# MCPEmulate1.net
KiCad netlist of a schematic drawn in Altium Designer
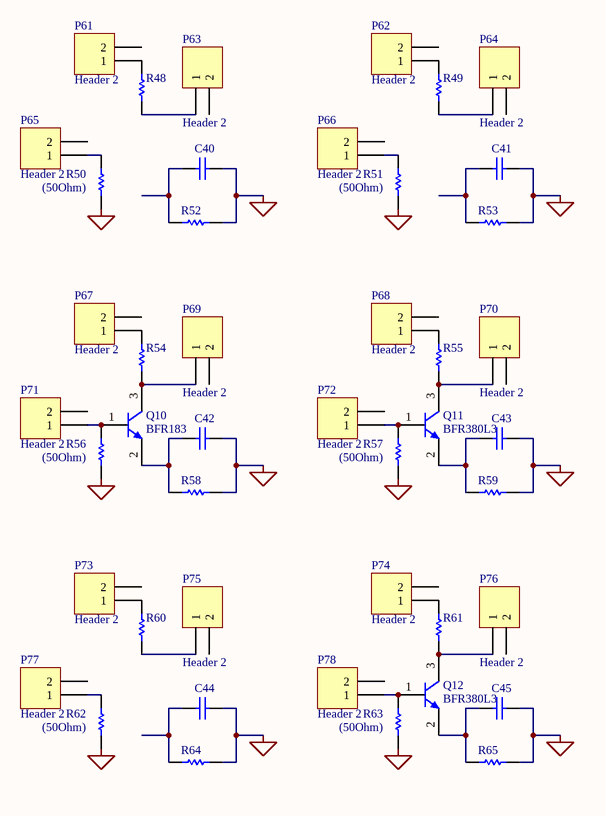
[diagram p0: MCPEmulate1.SchDoc]

(export (version "E")
  (design (tool "Eeschema 10.0.6"))
  (components
    (comp (ref "C40")
      (value "~")
      (footprint "CAPC2013X140X45NL15T25")
      (description "0402")
      (fields (field (name "PART NUMBER") "GRM21BR71A106KE51L") (field (name "MANUFACTURER") "Murata"))
      (libsource (lib "Altium Content Vault") (part "CAP"))
    )
    (comp (ref "C41")
      (value "~")
      (footprint "CAPC2013X140X45NL15T25")
      (description "0402")
      (fields (field (name "PART NUMBER") "GRM21BR71A106KE51L") (field (name "MANUFACTURER") "Murata"))
      (libsource (lib "Altium Content Vault") (part "CAP"))
    )
    (comp (ref "C42")
      (value "~")
      (footprint "CAPC2013X140X45NL15T25")
      (description "0402")
      (fields (field (name "PART NUMBER") "GRM21BR71A106KE51L") (field (name "MANUFACTURER") "Murata"))
      (libsource (lib "Altium Content Vault") (part "CAP"))
    )
    (comp (ref "C43")
      (value "~")
      (footprint "CAPC2013X140X45NL15T25")
      (description "0402")
      (fields (field (name "PART NUMBER") "GRM21BR71A106KE51L") (field (name "MANUFACTURER") "Murata"))
      (libsource (lib "Altium Content Vault") (part "CAP"))
    )
    (comp (ref "C44")
      (value "~")
      (footprint "CAPC2013X140X45NL15T25")
      (description "0402")
      (fields (field (name "PART NUMBER") "GRM21BR71A106KE51L") (field (name "MANUFACTURER") "Murata"))
      (libsource (lib "Altium Content Vault") (part "CAP"))
    )
    (comp (ref "C45")
      (value "~")
      (footprint "CAPC2013X140X45NL15T25")
      (description "0402")
      (fields (field (name "PART NUMBER") "GRM21BR71A106KE51L") (field (name "MANUFACTURER") "Murata"))
      (libsource (lib "Altium Content Vault") (part "CAP"))
    )
    (comp (ref "P61")
      (value "Header 2")
      (footprint "HDR1X2")
      (description "Header, 2-Pin")
      (fields (field (name "PUBLISHER") "Altium Limited"))
      (libsource (lib "Miscellaneous Connectors") (part "Header 2"))
    )
    (comp (ref "P62")
      (value "Header 2")
      (footprint "HDR1X2")
      (description "Header, 2-Pin")
      (fields (field (name "PUBLISHER") "Altium Limited"))
      (libsource (lib "Miscellaneous Connectors") (part "Header 2"))
    )
    (comp (ref "P63")
      (value "Header 2")
      (footprint "HDR1X2")
      (description "Header, 2-Pin")
      (fields (field (name "PUBLISHER") "Altium Limited"))
      (libsource (lib "") (part "Header 2_1"))
    )
    (comp (ref "P64")
      (value "Header 2")
      (footprint "HDR1X2")
      (description "Header, 2-Pin")
      (fields (field (name "PUBLISHER") "Altium Limited"))
      (libsource (lib "") (part "Header 2_1"))
    )
    (comp (ref "P65")
      (value "Header 2")
      (footprint "HDR1X2")
      (description "Header, 2-Pin")
      (fields (field (name "PUBLISHER") "Altium Limited"))
      (libsource (lib "Miscellaneous Connectors") (part "Header 2"))
    )
    (comp (ref "P66")
      (value "Header 2")
      (footprint "HDR1X2")
      (description "Header, 2-Pin")
      (fields (field (name "PUBLISHER") "Altium Limited"))
      (libsource (lib "Miscellaneous Connectors") (part "Header 2"))
    )
    (comp (ref "P67")
      (value "Header 2")
      (footprint "HDR1X2")
      (description "Header, 2-Pin")
      (fields (field (name "PUBLISHER") "Altium Limited"))
      (libsource (lib "Miscellaneous Connectors") (part "Header 2"))
    )
    (comp (ref "P68")
      (value "Header 2")
      (footprint "HDR1X2")
      (description "Header, 2-Pin")
      (fields (field (name "PUBLISHER") "Altium Limited"))
      (libsource (lib "Miscellaneous Connectors") (part "Header 2"))
    )
    (comp (ref "P69")
      (value "Header 2")
      (footprint "HDR1X2")
      (description "Header, 2-Pin")
      (fields (field (name "PUBLISHER") "Altium Limited"))
      (libsource (lib "") (part "Header 2_1"))
    )
    (comp (ref "P70")
      (value "Header 2")
      (footprint "HDR1X2")
      (description "Header, 2-Pin")
      (fields (field (name "PUBLISHER") "Altium Limited"))
      (libsource (lib "") (part "Header 2_1"))
    )
    (comp (ref "P71")
      (value "Header 2")
      (footprint "HDR1X2")
      (description "Header, 2-Pin")
      (fields (field (name "PUBLISHER") "Altium Limited"))
      (libsource (lib "Miscellaneous Connectors") (part "Header 2"))
    )
    (comp (ref "P72")
      (value "Header 2")
      (footprint "HDR1X2")
      (description "Header, 2-Pin")
      (fields (field (name "PUBLISHER") "Altium Limited"))
      (libsource (lib "Miscellaneous Connectors") (part "Header 2"))
    )
    (comp (ref "P73")
      (value "Header 2")
      (footprint "HDR1X2")
      (description "Header, 2-Pin")
      (fields (field (name "PUBLISHER") "Altium Limited"))
      (libsource (lib "Miscellaneous Connectors") (part "Header 2"))
    )
    (comp (ref "P74")
      (value "Header 2")
      (footprint "HDR1X2")
      (description "Header, 2-Pin")
      (fields (field (name "PUBLISHER") "Altium Limited"))
      (libsource (lib "Miscellaneous Connectors") (part "Header 2"))
    )
    (comp (ref "P75")
      (value "Header 2")
      (footprint "HDR1X2")
      (description "Header, 2-Pin")
      (fields (field (name "PUBLISHER") "Altium Limited"))
      (libsource (lib "") (part "Header 2_1"))
    )
    (comp (ref "P76")
      (value "Header 2")
      (footprint "HDR1X2")
      (description "Header, 2-Pin")
      (fields (field (name "PUBLISHER") "Altium Limited"))
      (libsource (lib "") (part "Header 2_1"))
    )
    (comp (ref "P77")
      (value "Header 2")
      (footprint "HDR1X2")
      (description "Header, 2-Pin")
      (fields (field (name "PUBLISHER") "Altium Limited"))
      (libsource (lib "Miscellaneous Connectors") (part "Header 2"))
    )
    (comp (ref "P78")
      (value "Header 2")
      (footprint "HDR1X2")
      (description "Header, 2-Pin")
      (fields (field (name "PUBLISHER") "Altium Limited"))
      (libsource (lib "Miscellaneous Connectors") (part "Header 2"))
    )
    (comp (ref "Q10")
      (value "BFR183")
      (footprint "INF-SOT23_M")
      (description "NPN Silicon RF Transistor, 12 V VCEO, 65 mA IC, 17.5 dB Gmax, SOT23, Green")
      (fields (field (name "MANUFACTURER") "Infineon"))
      (libsource (lib "Altium Content Vault") (part "INF-BFR183-3"))
    )
    (comp (ref "Q11")
      (value "BFR380L3")
      (footprint "INF-TSLP-3-1_V")
      (description "NPN Silicon RF Transistor, 6 V VCEO, 80 mA IC, 13.5 dB Gmax, TSLP-3-1, Green")
      (fields (field (name "MANUFACTURER") "Infineon"))
      (libsource (lib "Altium Content Vault") (part "INF-BFR380L3-3"))
    )
    (comp (ref "Q12")
      (value "BFR380L3")
      (footprint "INF-TSLP-3-1_V")
      (description "NPN Silicon RF Transistor, 6 V VCEO, 80 mA IC, 13.5 dB Gmax, TSLP-3-1, Green")
      (fields (field (name "MANUFACTURER") "Infineon"))
      (libsource (lib "Altium Content Vault") (part "INF-BFR380L3-3"))
    )
    (comp (ref "R48")
      (value "~")
      (footprint "RESC1005X40X25NL05T10")
      (description "0402")
      (fields (field (name "PART NUMBER") "RC0402FR-071KL") (field (name "MANUFACTURER") "Yageo / Phycomp"))
      (libsource (lib "Altium Content Vault") (part "RES"))
    )
    (comp (ref "R49")
      (value "~")
      (footprint "RESC1005X40X25NL05T10")
      (description "0402")
      (fields (field (name "PART NUMBER") "RC0402FR-071KL") (field (name "MANUFACTURER") "Yageo / Phycomp"))
      (libsource (lib "Altium Content Vault") (part "RES"))
    )
    (comp (ref "R50")
      (value "(50Ohm)")
      (footprint "RESC1005X40X25NL05T10")
      (description "0402")
      (fields (field (name "PART NUMBER") "RC0402FR-071KL") (field (name "MANUFACTURER") "Yageo / Phycomp"))
      (libsource (lib "Altium Content Vault") (part "RES"))
    )
    (comp (ref "R51")
      (value "(50Ohm)")
      (footprint "RESC1005X40X25NL05T10")
      (description "0402")
      (fields (field (name "PART NUMBER") "RC0402FR-071KL") (field (name "MANUFACTURER") "Yageo / Phycomp"))
      (libsource (lib "Altium Content Vault") (part "RES"))
    )
    (comp (ref "R52")
      (value "~")
      (footprint "RESC1005X40X25NL05T10")
      (description "0402")
      (fields (field (name "PART NUMBER") "RC0402FR-071KL") (field (name "MANUFACTURER") "Yageo / Phycomp"))
      (libsource (lib "Altium Content Vault") (part "RES"))
    )
    (comp (ref "R53")
      (value "~")
      (footprint "RESC1005X40X25NL05T10")
      (description "0402")
      (fields (field (name "PART NUMBER") "RC0402FR-071KL") (field (name "MANUFACTURER") "Yageo / Phycomp"))
      (libsource (lib "Altium Content Vault") (part "RES"))
    )
    (comp (ref "R54")
      (value "~")
      (footprint "RESC1005X40X25NL05T10")
      (description "0402")
      (fields (field (name "PART NUMBER") "RC0402FR-071KL") (field (name "MANUFACTURER") "Yageo / Phycomp"))
      (libsource (lib "Altium Content Vault") (part "RES"))
    )
    (comp (ref "R55")
      (value "~")
      (footprint "RESC1005X40X25NL05T10")
      (description "0402")
      (fields (field (name "PART NUMBER") "RC0402FR-071KL") (field (name "MANUFACTURER") "Yageo / Phycomp"))
      (libsource (lib "Altium Content Vault") (part "RES"))
    )
    (comp (ref "R56")
      (value "(50Ohm)")
      (footprint "RESC1005X40X25NL05T10")
      (description "0402")
      (fields (field (name "PART NUMBER") "RC0402FR-071KL") (field (name "MANUFACTURER") "Yageo / Phycomp"))
      (libsource (lib "Altium Content Vault") (part "RES"))
    )
    (comp (ref "R57")
      (value "(50Ohm)")
      (footprint "RESC1005X40X25NL05T10")
      (description "0402")
      (fields (field (name "PART NUMBER") "RC0402FR-071KL") (field (name "MANUFACTURER") "Yageo / Phycomp"))
      (libsource (lib "Altium Content Vault") (part "RES"))
    )
    (comp (ref "R58")
      (value "~")
      (footprint "RESC1005X40X25NL05T10")
      (description "0402")
      (fields (field (name "PART NUMBER") "RC0402FR-071KL") (field (name "MANUFACTURER") "Yageo / Phycomp"))
      (libsource (lib "Altium Content Vault") (part "RES"))
    )
    (comp (ref "R59")
      (value "~")
      (footprint "RESC1005X40X25NL05T10")
      (description "0402")
      (fields (field (name "PART NUMBER") "RC0402FR-071KL") (field (name "MANUFACTURER") "Yageo / Phycomp"))
      (libsource (lib "Altium Content Vault") (part "RES"))
    )
    (comp (ref "R60")
      (value "~")
      (footprint "RESC1005X40X25NL05T10")
      (description "0402")
      (fields (field (name "PART NUMBER") "RC0402FR-071KL") (field (name "MANUFACTURER") "Yageo / Phycomp"))
      (libsource (lib "Altium Content Vault") (part "RES"))
    )
    (comp (ref "R61")
      (value "~")
      (footprint "RESC1005X40X25NL05T10")
      (description "0402")
      (fields (field (name "PART NUMBER") "RC0402FR-071KL") (field (name "MANUFACTURER") "Yageo / Phycomp"))
      (libsource (lib "Altium Content Vault") (part "RES"))
    )
    (comp (ref "R62")
      (value "(50Ohm)")
      (footprint "RESC1005X40X25NL05T10")
      (description "0402")
      (fields (field (name "PART NUMBER") "RC0402FR-071KL") (field (name "MANUFACTURER") "Yageo / Phycomp"))
      (libsource (lib "Altium Content Vault") (part "RES"))
    )
    (comp (ref "R63")
      (value "(50Ohm)")
      (footprint "RESC1005X40X25NL05T10")
      (description "0402")
      (fields (field (name "PART NUMBER") "RC0402FR-071KL") (field (name "MANUFACTURER") "Yageo / Phycomp"))
      (libsource (lib "Altium Content Vault") (part "RES"))
    )
    (comp (ref "R64")
      (value "~")
      (footprint "RESC1005X40X25NL05T10")
      (description "0402")
      (fields (field (name "PART NUMBER") "RC0402FR-071KL") (field (name "MANUFACTURER") "Yageo / Phycomp"))
      (libsource (lib "Altium Content Vault") (part "RES"))
    )
    (comp (ref "R65")
      (value "~")
      (footprint "RESC1005X40X25NL05T10")
      (description "0402")
      (fields (field (name "PART NUMBER") "RC0402FR-071KL") (field (name "MANUFACTURER") "Yageo / Phycomp"))
      (libsource (lib "Altium Content Vault") (part "RES"))
    )
  )
  (nets
    (net (code "1") (name "GND") (class "Default")
      (node (ref "C40") (pin "1") (pinfunction "1_1") (pintype "passive"))
      (node (ref "C41") (pin "1") (pinfunction "1_1") (pintype "passive"))
      (node (ref "C42") (pin "1") (pinfunction "1_1") (pintype "passive"))
      (node (ref "C43") (pin "1") (pinfunction "1_1") (pintype "passive"))
      (node (ref "C44") (pin "1") (pinfunction "1_1") (pintype "passive"))
      (node (ref "C45") (pin "1") (pinfunction "1_1") (pintype "passive"))
      (node (ref "R50") (pin "1") (pinfunction "1_1") (pintype "passive"))
      (node (ref "R51") (pin "1") (pinfunction "1_1") (pintype "passive"))
      (node (ref "R52") (pin "1") (pinfunction "1_1") (pintype "passive"))
      (node (ref "R53") (pin "1") (pinfunction "1_1") (pintype "passive"))
      (node (ref "R56") (pin "1") (pinfunction "1_1") (pintype "passive"))
      (node (ref "R57") (pin "1") (pinfunction "1_1") (pintype "passive"))
      (node (ref "R58") (pin "1") (pinfunction "1_1") (pintype "passive"))
      (node (ref "R59") (pin "1") (pinfunction "1_1") (pintype "passive"))
      (node (ref "R62") (pin "1") (pinfunction "1_1") (pintype "passive"))
      (node (ref "R63") (pin "1") (pinfunction "1_1") (pintype "passive"))
      (node (ref "R64") (pin "1") (pinfunction "1_1") (pintype "passive"))
      (node (ref "R65") (pin "1") (pinfunction "1_1") (pintype "passive"))
    )
    (net (code "2") (name "Net-(C40-Pad2)") (class "Default")
      (node (ref "C40") (pin "2") (pinfunction "2_2") (pintype "passive"))
      (node (ref "R52") (pin "2") (pinfunction "2_2") (pintype "passive"))
    )
    (net (code "3") (name "Net-(C41-Pad2)") (class "Default")
      (node (ref "C41") (pin "2") (pinfunction "2_2") (pintype "passive"))
      (node (ref "R53") (pin "2") (pinfunction "2_2") (pintype "passive"))
    )
    (net (code "4") (name "Net-(C44-Pad2)") (class "Default")
      (node (ref "C44") (pin "2") (pinfunction "2_2") (pintype "passive"))
      (node (ref "R64") (pin "2") (pinfunction "2_2") (pintype "passive"))
    )
    (net (code "5") (name "Net-(P61-Pad1)") (class "Default")
      (node (ref "P61") (pin "1") (pinfunction "1_1") (pintype "passive"))
      (node (ref "R48") (pin "1") (pinfunction "1_1") (pintype "passive"))
    )
    (net (code "6") (name "Net-(P62-Pad1)") (class "Default")
      (node (ref "P62") (pin "1") (pinfunction "1_1") (pintype "passive"))
      (node (ref "R49") (pin "1") (pinfunction "1_1") (pintype "passive"))
    )
    (net (code "7") (name "Net-(P63-Pad1)") (class "Default")
      (node (ref "P63") (pin "1") (pinfunction "1_1") (pintype "passive"))
      (node (ref "R48") (pin "2") (pinfunction "2_2") (pintype "passive"))
    )
    (net (code "8") (name "Net-(P64-Pad1)") (class "Default")
      (node (ref "P64") (pin "1") (pinfunction "1_1") (pintype "passive"))
      (node (ref "R49") (pin "2") (pinfunction "2_2") (pintype "passive"))
    )
    (net (code "9") (name "Net-(P65-Pad1)") (class "Default")
      (node (ref "P65") (pin "1") (pinfunction "1_1") (pintype "passive"))
      (node (ref "R50") (pin "2") (pinfunction "2_2") (pintype "passive"))
    )
    (net (code "10") (name "Net-(P66-Pad1)") (class "Default")
      (node (ref "P66") (pin "1") (pinfunction "1_1") (pintype "passive"))
      (node (ref "R51") (pin "2") (pinfunction "2_2") (pintype "passive"))
    )
    (net (code "11") (name "Net-(P67-Pad1)") (class "Default")
      (node (ref "P67") (pin "1") (pinfunction "1_1") (pintype "passive"))
      (node (ref "R54") (pin "1") (pinfunction "1_1") (pintype "passive"))
    )
    (net (code "12") (name "Net-(P68-Pad1)") (class "Default")
      (node (ref "P68") (pin "1") (pinfunction "1_1") (pintype "passive"))
      (node (ref "R55") (pin "1") (pinfunction "1_1") (pintype "passive"))
    )
    (net (code "13") (name "Net-(P73-Pad1)") (class "Default")
      (node (ref "P73") (pin "1") (pinfunction "1_1") (pintype "passive"))
      (node (ref "R60") (pin "1") (pinfunction "1_1") (pintype "passive"))
    )
    (net (code "14") (name "Net-(P74-Pad1)") (class "Default")
      (node (ref "P74") (pin "1") (pinfunction "1_1") (pintype "passive"))
      (node (ref "R61") (pin "1") (pinfunction "1_1") (pintype "passive"))
    )
    (net (code "15") (name "Net-(P75-Pad1)") (class "Default")
      (node (ref "P75") (pin "1") (pinfunction "1_1") (pintype "passive"))
      (node (ref "R60") (pin "2") (pinfunction "2_2") (pintype "passive"))
    )
    (net (code "16") (name "Net-(P77-Pad1)") (class "Default")
      (node (ref "P77") (pin "1") (pinfunction "1_1") (pintype "passive"))
      (node (ref "R62") (pin "2") (pinfunction "2_2") (pintype "passive"))
    )
    (net (code "17") (name "Net-(Q10-B)") (class "Default")
      (node (ref "P71") (pin "1") (pinfunction "1_1") (pintype "passive"))
      (node (ref "Q10") (pin "1") (pinfunction "B_1") (pintype "passive"))
      (node (ref "R56") (pin "2") (pinfunction "2_2") (pintype "passive"))
    )
    (net (code "18") (name "Net-(Q10-C)") (class "Default")
      (node (ref "P69") (pin "1") (pinfunction "1_1") (pintype "passive"))
      (node (ref "Q10") (pin "3") (pinfunction "C_3") (pintype "passive"))
      (node (ref "R54") (pin "2") (pinfunction "2_2") (pintype "passive"))
    )
    (net (code "19") (name "Net-(Q10-E)") (class "Default")
      (node (ref "C42") (pin "2") (pinfunction "2_2") (pintype "passive"))
      (node (ref "Q10") (pin "2") (pinfunction "E_2") (pintype "passive"))
      (node (ref "R58") (pin "2") (pinfunction "2_2") (pintype "passive"))
    )
    (net (code "20") (name "Net-(Q11-B)") (class "Default")
      (node (ref "P72") (pin "1") (pinfunction "1_1") (pintype "passive"))
      (node (ref "Q11") (pin "1") (pinfunction "B_1") (pintype "passive"))
      (node (ref "R57") (pin "2") (pinfunction "2_2") (pintype "passive"))
    )
    (net (code "21") (name "Net-(Q11-C)") (class "Default")
      (node (ref "P70") (pin "1") (pinfunction "1_1") (pintype "passive"))
      (node (ref "Q11") (pin "3") (pinfunction "C_3") (pintype "passive"))
      (node (ref "R55") (pin "2") (pinfunction "2_2") (pintype "passive"))
    )
    (net (code "22") (name "Net-(Q11-E)") (class "Default")
      (node (ref "C43") (pin "2") (pinfunction "2_2") (pintype "passive"))
      (node (ref "Q11") (pin "2") (pinfunction "E_2") (pintype "passive"))
      (node (ref "R59") (pin "2") (pinfunction "2_2") (pintype "passive"))
    )
    (net (code "23") (name "Net-(Q12-B)") (class "Default")
      (node (ref "P78") (pin "1") (pinfunction "1_1") (pintype "passive"))
      (node (ref "Q12") (pin "1") (pinfunction "B_1") (pintype "passive"))
      (node (ref "R63") (pin "2") (pinfunction "2_2") (pintype "passive"))
    )
    (net (code "24") (name "Net-(Q12-C)") (class "Default")
      (node (ref "P76") (pin "1") (pinfunction "1_1") (pintype "passive"))
      (node (ref "Q12") (pin "3") (pinfunction "C_3") (pintype "passive"))
      (node (ref "R61") (pin "2") (pinfunction "2_2") (pintype "passive"))
    )
    (net (code "25") (name "Net-(Q12-E)") (class "Default")
      (node (ref "C45") (pin "2") (pinfunction "2_2") (pintype "passive"))
      (node (ref "Q12") (pin "2") (pinfunction "E_2") (pintype "passive"))
      (node (ref "R65") (pin "2") (pinfunction "2_2") (pintype "passive"))
    )
    (net (code "26") (name "unconnected-(P61-Pad2)") (class "Default")
      (node (ref "P61") (pin "2") (pinfunction "2_2") (pintype "passive"))
    )
    (net (code "27") (name "unconnected-(P62-Pad2)") (class "Default")
      (node (ref "P62") (pin "2") (pinfunction "2_2") (pintype "passive"))
    )
    (net (code "28") (name "unconnected-(P63-Pad2)") (class "Default")
      (node (ref "P63") (pin "2") (pinfunction "2_2") (pintype "passive"))
    )
    (net (code "29") (name "unconnected-(P64-Pad2)") (class "Default")
      (node (ref "P64") (pin "2") (pinfunction "2_2") (pintype "passive"))
    )
    (net (code "30") (name "unconnected-(P65-Pad2)") (class "Default")
      (node (ref "P65") (pin "2") (pinfunction "2_2") (pintype "passive"))
    )
    (net (code "31") (name "unconnected-(P66-Pad2)") (class "Default")
      (node (ref "P66") (pin "2") (pinfunction "2_2") (pintype "passive"))
    )
    (net (code "32") (name "unconnected-(P67-Pad2)") (class "Default")
      (node (ref "P67") (pin "2") (pinfunction "2_2") (pintype "passive"))
    )
    (net (code "33") (name "unconnected-(P68-Pad2)") (class "Default")
      (node (ref "P68") (pin "2") (pinfunction "2_2") (pintype "passive"))
    )
    (net (code "34") (name "unconnected-(P69-Pad2)") (class "Default")
      (node (ref "P69") (pin "2") (pinfunction "2_2") (pintype "passive"))
    )
    (net (code "35") (name "unconnected-(P70-Pad2)") (class "Default")
      (node (ref "P70") (pin "2") (pinfunction "2_2") (pintype "passive"))
    )
    (net (code "36") (name "unconnected-(P71-Pad2)") (class "Default")
      (node (ref "P71") (pin "2") (pinfunction "2_2") (pintype "passive"))
    )
    (net (code "37") (name "unconnected-(P72-Pad2)") (class "Default")
      (node (ref "P72") (pin "2") (pinfunction "2_2") (pintype "passive"))
    )
    (net (code "38") (name "unconnected-(P73-Pad2)") (class "Default")
      (node (ref "P73") (pin "2") (pinfunction "2_2") (pintype "passive"))
    )
    (net (code "39") (name "unconnected-(P74-Pad2)") (class "Default")
      (node (ref "P74") (pin "2") (pinfunction "2_2") (pintype "passive"))
    )
    (net (code "40") (name "unconnected-(P75-Pad2)") (class "Default")
      (node (ref "P75") (pin "2") (pinfunction "2_2") (pintype "passive"))
    )
    (net (code "41") (name "unconnected-(P76-Pad2)") (class "Default")
      (node (ref "P76") (pin "2") (pinfunction "2_2") (pintype "passive"))
    )
    (net (code "42") (name "unconnected-(P77-Pad2)") (class "Default")
      (node (ref "P77") (pin "2") (pinfunction "2_2") (pintype "passive"))
    )
    (net (code "43") (name "unconnected-(P78-Pad2)") (class "Default")
      (node (ref "P78") (pin "2") (pinfunction "2_2") (pintype "passive"))
    )
  )
)
